# schmatic2.net
KiCad netlist of a schematic drawn in EAGLE
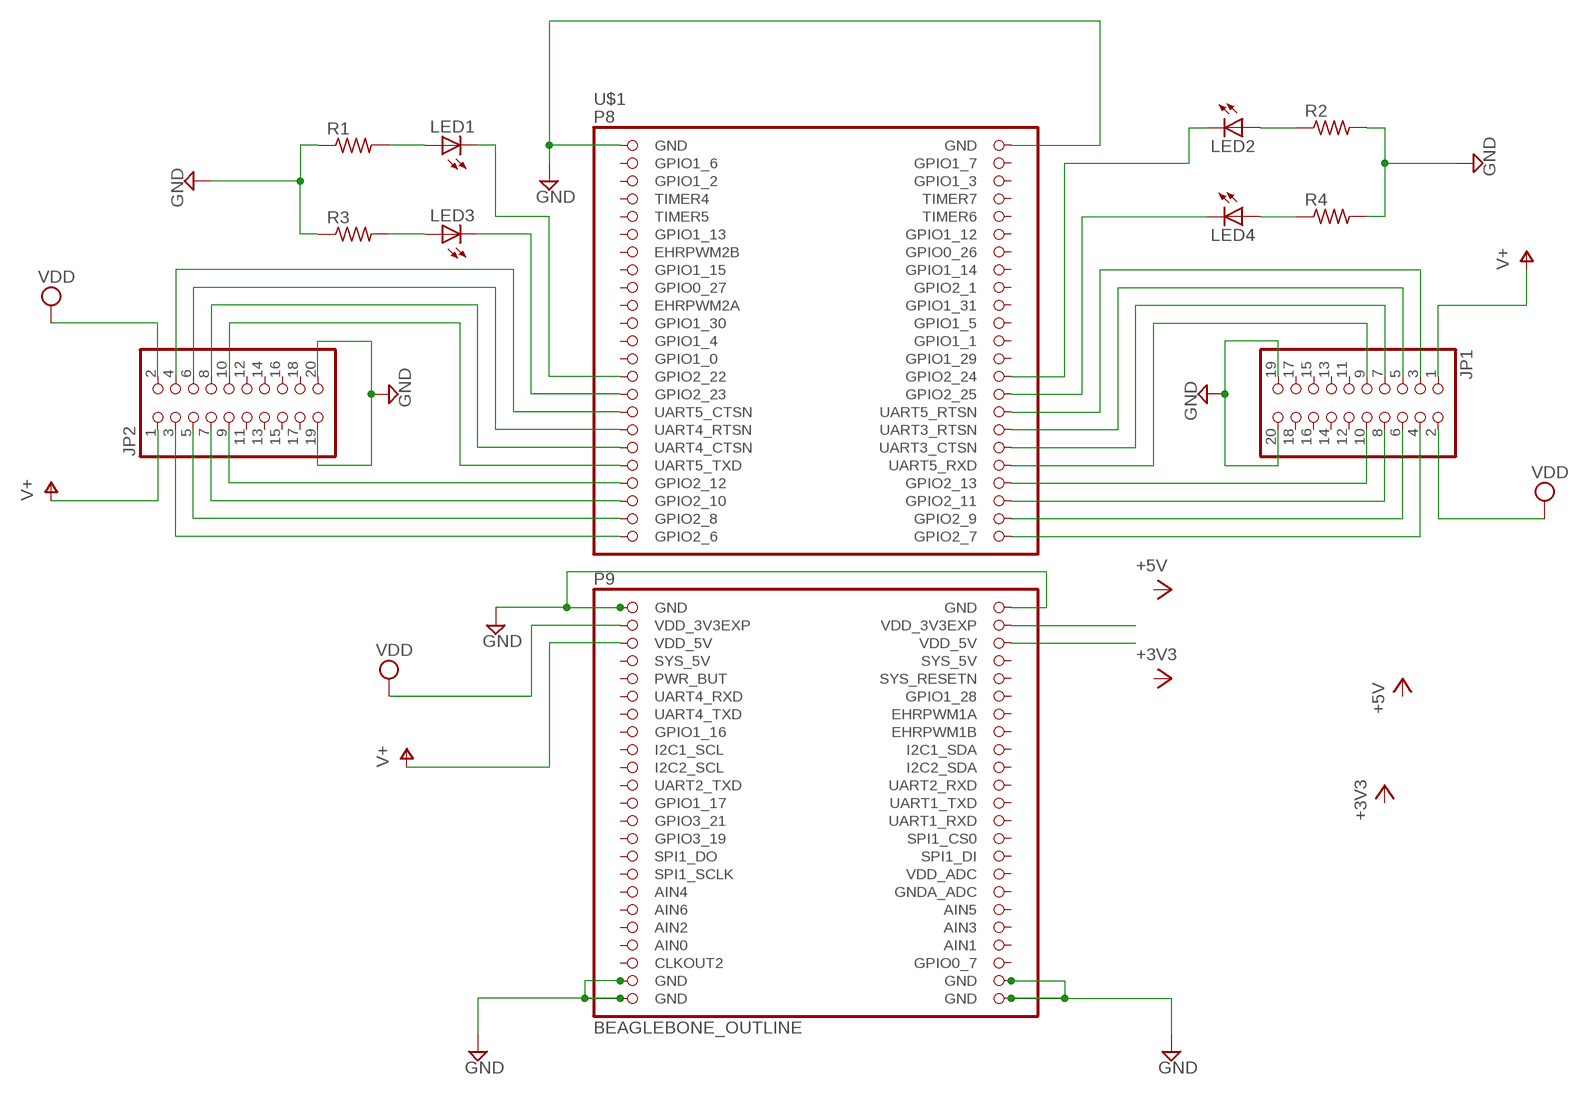
[diagram p0: schematic, sheet 1]

(export (version "E")
  (design (tool "Eeschema 10.0.6"))
  (components
    (comp (ref "JP1")
      (value "PINHD-2X10")
      (footprint "eagle-import:2X10")
      (libsource (lib "eagle-import") (part "PINHD-2X10"))
    )
    (comp (ref "JP2")
      (value "PINHD-2X10")
      (footprint "eagle-import:2X10")
      (libsource (lib "eagle-import") (part "PINHD-2X10"))
    )
    (comp (ref "LED1")
      (value "LED3MM")
      (footprint "eagle-import:LED3MM")
      (libsource (lib "eagle-import") (part "LED3MM"))
    )
    (comp (ref "LED2")
      (value "LED3MM")
      (footprint "eagle-import:LED3MM")
      (libsource (lib "eagle-import") (part "LED3MM"))
    )
    (comp (ref "LED3")
      (value "LED3MM")
      (footprint "eagle-import:LED3MM")
      (libsource (lib "eagle-import") (part "LED3MM"))
    )
    (comp (ref "LED4")
      (value "LED3MM")
      (footprint "eagle-import:LED3MM")
      (libsource (lib "eagle-import") (part "LED3MM"))
    )
    (comp (ref "R1")
      (value "R-US_0309/12")
      (footprint "eagle-import:0309_12")
      (libsource (lib "eagle-import") (part "R-US_0309/12"))
    )
    (comp (ref "R2")
      (value "R-US_0309/12")
      (footprint "eagle-import:0309_12")
      (libsource (lib "eagle-import") (part "R-US_0309/12"))
    )
    (comp (ref "R3")
      (value "R-US_0309/12")
      (footprint "eagle-import:0309_12")
      (libsource (lib "eagle-import") (part "R-US_0309/12"))
    )
    (comp (ref "R4")
      (value "R-US_0309/12")
      (footprint "eagle-import:0309_12")
      (libsource (lib "eagle-import") (part "R-US_0309/12"))
    )
    (comp (ref "U$1")
      (value "BEAGLEBONE_OUTLINE")
      (footprint "eagle-import:BEAGLEBONE_SHIELD")
      (libsource (lib "eagle-import") (part "BEAGLEBONE_OUTLINE"))
    )
  )
  (nets
    (net (code "3") (name "/AIN0") (class "Default")
      (node (ref "U$1") (pin "85") (pinfunction "AIN0_85") (pintype "power_in"))
    )
    (net (code "4") (name "/SYS_5V") (class "Default")
      (node (ref "U$1") (pin "53") (pinfunction "SYS_5V_53") (pintype "power_in"))
    )
    (net (code "5") (name "GND") (class "Default")
      (node (ref "JP1") (pin "19") (pinfunction "19_19") (pintype "passive"))
      (node (ref "JP1") (pin "20") (pinfunction "20_20") (pintype "passive"))
      (node (ref "JP2") (pin "19") (pinfunction "19_19") (pintype "passive"))
      (node (ref "JP2") (pin "20") (pinfunction "20_20") (pintype "passive"))
      (node (ref "R1") (pin "1") (pinfunction "1_1") (pintype "passive"))
      (node (ref "R2") (pin "2") (pinfunction "2_2") (pintype "passive"))
      (node (ref "R3") (pin "1") (pinfunction "1_1") (pintype "passive"))
      (node (ref "R4") (pin "2") (pinfunction "2_2") (pintype "passive"))
      (node (ref "U$1") (pin "1") (pinfunction "GND_1") (pintype "power_in"))
      (node (ref "U$1") (pin "2") (pinfunction "GND_2") (pintype "power_in"))
      (node (ref "U$1") (pin "47") (pinfunction "GND_47") (pintype "power_in"))
      (node (ref "U$1") (pin "48") (pinfunction "GND_48") (pintype "power_in"))
      (node (ref "U$1") (pin "89") (pinfunction "GND_89") (pintype "power_in"))
      (node (ref "U$1") (pin "90") (pinfunction "GND_90") (pintype "power_in"))
      (node (ref "U$1") (pin "91") (pinfunction "GND_91") (pintype "power_in"))
      (node (ref "U$1") (pin "92") (pinfunction "GND_92") (pintype "power_in"))
    )
    (net (code "6") (name "Net-(LED1-C)") (class "Default")
      (node (ref "LED1") (pin "K") (pinfunction "C_K") (pintype "passive"))
      (node (ref "U$1") (pin "27") (pinfunction "GPIO2_22_27") (pintype "passive"))
    )
    (net (code "7") (name "Net-(LED1-PadA)") (class "Default")
      (node (ref "LED1") (pin "A") (pinfunction "A_A") (pintype "passive"))
      (node (ref "R1") (pin "2") (pinfunction "2_2") (pintype "passive"))
    )
    (net (code "8") (name "Net-(LED2-C)") (class "Default")
      (node (ref "LED2") (pin "K") (pinfunction "C_K") (pintype "passive"))
      (node (ref "U$1") (pin "28") (pinfunction "GPIO2_24_28") (pintype "passive"))
    )
    (net (code "9") (name "Net-(LED2-PadA)") (class "Default")
      (node (ref "LED2") (pin "A") (pinfunction "A_A") (pintype "passive"))
      (node (ref "R2") (pin "1") (pinfunction "1_1") (pintype "passive"))
    )
    (net (code "10") (name "Net-(LED3-C)") (class "Default")
      (node (ref "LED3") (pin "K") (pinfunction "C_K") (pintype "passive"))
      (node (ref "U$1") (pin "29") (pinfunction "GPIO2_23_29") (pintype "passive"))
    )
    (net (code "11") (name "Net-(LED3-PadA)") (class "Default")
      (node (ref "LED3") (pin "A") (pinfunction "A_A") (pintype "passive"))
      (node (ref "R3") (pin "2") (pinfunction "2_2") (pintype "passive"))
    )
    (net (code "12") (name "Net-(LED4-C)") (class "Default")
      (node (ref "LED4") (pin "K") (pinfunction "C_K") (pintype "passive"))
      (node (ref "U$1") (pin "30") (pinfunction "GPIO2_25_30") (pintype "passive"))
    )
    (net (code "13") (name "Net-(LED4-PadA)") (class "Default")
      (node (ref "LED4") (pin "A") (pinfunction "A_A") (pintype "passive"))
      (node (ref "R4") (pin "1") (pinfunction "1_1") (pintype "passive"))
    )
    (net (code "14") (name "Net-(U$1-GPIO2_6)") (class "Default")
      (node (ref "JP2") (pin "3") (pinfunction "3_3") (pintype "passive"))
      (node (ref "U$1") (pin "45") (pinfunction "GPIO2_6_45") (pintype "passive"))
    )
    (net (code "15") (name "Net-(U$1-GPIO2_7)") (class "Default")
      (node (ref "JP1") (pin "4") (pinfunction "4_4") (pintype "passive"))
      (node (ref "U$1") (pin "46") (pinfunction "GPIO2_7_46") (pintype "passive"))
    )
    (net (code "16") (name "Net-(U$1-GPIO2_8)") (class "Default")
      (node (ref "JP2") (pin "5") (pinfunction "5_5") (pintype "passive"))
      (node (ref "U$1") (pin "43") (pinfunction "GPIO2_8_43") (pintype "passive"))
    )
    (net (code "17") (name "Net-(U$1-GPIO2_9)") (class "Default")
      (node (ref "JP1") (pin "6") (pinfunction "6_6") (pintype "passive"))
      (node (ref "U$1") (pin "44") (pinfunction "GPIO2_9_44") (pintype "passive"))
    )
    (net (code "18") (name "Net-(U$1-GPIO2_10)") (class "Default")
      (node (ref "JP2") (pin "7") (pinfunction "7_7") (pintype "passive"))
      (node (ref "U$1") (pin "41") (pinfunction "GPIO2_10_41") (pintype "passive"))
    )
    (net (code "19") (name "Net-(U$1-GPIO2_11)") (class "Default")
      (node (ref "JP1") (pin "8") (pinfunction "8_8") (pintype "passive"))
      (node (ref "U$1") (pin "42") (pinfunction "GPIO2_11_42") (pintype "passive"))
    )
    (net (code "20") (name "Net-(U$1-GPIO2_12)") (class "Default")
      (node (ref "JP2") (pin "9") (pinfunction "9_9") (pintype "passive"))
      (node (ref "U$1") (pin "39") (pinfunction "GPIO2_12_39") (pintype "passive"))
    )
    (net (code "21") (name "Net-(U$1-GPIO2_13)") (class "Default")
      (node (ref "JP1") (pin "10") (pinfunction "10_10") (pintype "passive"))
      (node (ref "U$1") (pin "40") (pinfunction "GPIO2_13_40") (pintype "passive"))
    )
    (net (code "22") (name "Net-(U$1-UART3_CTSN)") (class "Default")
      (node (ref "JP1") (pin "7") (pinfunction "7_7") (pintype "passive"))
      (node (ref "U$1") (pin "36") (pinfunction "UART3_CTSN_36") (pintype "passive"))
    )
    (net (code "23") (name "Net-(U$1-UART3_RTSN)") (class "Default")
      (node (ref "JP1") (pin "5") (pinfunction "5_5") (pintype "passive"))
      (node (ref "U$1") (pin "34") (pinfunction "UART3_RTSN_34") (pintype "passive"))
    )
    (net (code "24") (name "Net-(U$1-UART4_CTSN)") (class "Default")
      (node (ref "JP2") (pin "8") (pinfunction "8_8") (pintype "passive"))
      (node (ref "U$1") (pin "35") (pinfunction "UART4_CTSN_35") (pintype "passive"))
    )
    (net (code "25") (name "Net-(U$1-UART4_RTSN)") (class "Default")
      (node (ref "JP2") (pin "6") (pinfunction "6_6") (pintype "passive"))
      (node (ref "U$1") (pin "33") (pinfunction "UART4_RTSN_33") (pintype "passive"))
    )
    (net (code "26") (name "Net-(U$1-UART5_CTSN)") (class "Default")
      (node (ref "JP2") (pin "4") (pinfunction "4_4") (pintype "passive"))
      (node (ref "U$1") (pin "31") (pinfunction "UART5_CTSN_31") (pintype "passive"))
    )
    (net (code "27") (name "Net-(U$1-UART5_RTSN)") (class "Default")
      (node (ref "JP1") (pin "3") (pinfunction "3_3") (pintype "passive"))
      (node (ref "U$1") (pin "32") (pinfunction "UART5_RTSN_32") (pintype "passive"))
    )
    (net (code "28") (name "Net-(U$1-UART5_RXD)") (class "Default")
      (node (ref "JP1") (pin "9") (pinfunction "9_9") (pintype "passive"))
      (node (ref "U$1") (pin "38") (pinfunction "UART5_RXD_38") (pintype "passive"))
    )
    (net (code "29") (name "Net-(U$1-UART5_TXD)") (class "Default")
      (node (ref "JP2") (pin "10") (pinfunction "10_10") (pintype "passive"))
      (node (ref "U$1") (pin "37") (pinfunction "UART5_TXD_37") (pintype "passive"))
    )
    (net (code "30") (name "V+") (class "Default")
      (node (ref "JP1") (pin "1") (pinfunction "1_1") (pintype "passive"))
      (node (ref "JP2") (pin "1") (pinfunction "1_1") (pintype "passive"))
      (node (ref "U$1") (pin "51") (pinfunction "VDD_5V_51") (pintype "power_in"))
    )
    (net (code "31") (name "VDD") (class "Default")
      (node (ref "JP1") (pin "2") (pinfunction "2_2") (pintype "passive"))
      (node (ref "JP2") (pin "2") (pinfunction "2_2") (pintype "passive"))
      (node (ref "U$1") (pin "49") (pinfunction "VDD_3V3EXP_49") (pintype "power_in"))
    )
    (net (code "32") (name "unconnected-(JP1-Pad11)") (class "Default")
      (node (ref "JP1") (pin "11") (pinfunction "11_11") (pintype "passive"))
    )
    (net (code "33") (name "unconnected-(JP1-Pad12)") (class "Default")
      (node (ref "JP1") (pin "12") (pinfunction "12_12") (pintype "passive"))
    )
    (net (code "34") (name "unconnected-(JP1-Pad13)") (class "Default")
      (node (ref "JP1") (pin "13") (pinfunction "13_13") (pintype "passive"))
    )
    (net (code "35") (name "unconnected-(JP1-Pad14)") (class "Default")
      (node (ref "JP1") (pin "14") (pinfunction "14_14") (pintype "passive"))
    )
    (net (code "36") (name "unconnected-(JP1-Pad15)") (class "Default")
      (node (ref "JP1") (pin "15") (pinfunction "15_15") (pintype "passive"))
    )
    (net (code "37") (name "unconnected-(JP1-Pad16)") (class "Default")
      (node (ref "JP1") (pin "16") (pinfunction "16_16") (pintype "passive"))
    )
    (net (code "38") (name "unconnected-(JP1-Pad17)") (class "Default")
      (node (ref "JP1") (pin "17") (pinfunction "17_17") (pintype "passive"))
    )
    (net (code "39") (name "unconnected-(JP1-Pad18)") (class "Default")
      (node (ref "JP1") (pin "18") (pinfunction "18_18") (pintype "passive"))
    )
    (net (code "40") (name "unconnected-(JP2-Pad11)") (class "Default")
      (node (ref "JP2") (pin "11") (pinfunction "11_11") (pintype "passive"))
    )
    (net (code "41") (name "unconnected-(JP2-Pad12)") (class "Default")
      (node (ref "JP2") (pin "12") (pinfunction "12_12") (pintype "passive"))
    )
    (net (code "42") (name "unconnected-(JP2-Pad13)") (class "Default")
      (node (ref "JP2") (pin "13") (pinfunction "13_13") (pintype "passive"))
    )
    (net (code "43") (name "unconnected-(JP2-Pad14)") (class "Default")
      (node (ref "JP2") (pin "14") (pinfunction "14_14") (pintype "passive"))
    )
    (net (code "44") (name "unconnected-(JP2-Pad15)") (class "Default")
      (node (ref "JP2") (pin "15") (pinfunction "15_15") (pintype "passive"))
    )
    (net (code "45") (name "unconnected-(JP2-Pad16)") (class "Default")
      (node (ref "JP2") (pin "16") (pinfunction "16_16") (pintype "passive"))
    )
    (net (code "46") (name "unconnected-(JP2-Pad17)") (class "Default")
      (node (ref "JP2") (pin "17") (pinfunction "17_17") (pintype "passive"))
    )
    (net (code "47") (name "unconnected-(JP2-Pad18)") (class "Default")
      (node (ref "JP2") (pin "18") (pinfunction "18_18") (pintype "passive"))
    )
    (net (code "48") (name "unconnected-(U$1-AIN1-Pad86)") (class "Default")
      (node (ref "U$1") (pin "86") (pinfunction "AIN1_86") (pintype "passive"))
    )
    (net (code "49") (name "unconnected-(U$1-AIN2-Pad83)") (class "Default")
      (node (ref "U$1") (pin "83") (pinfunction "AIN2_83") (pintype "passive"))
    )
    (net (code "50") (name "unconnected-(U$1-AIN3-Pad84)") (class "Default")
      (node (ref "U$1") (pin "84") (pinfunction "AIN3_84") (pintype "passive"))
    )
    (net (code "51") (name "unconnected-(U$1-AIN4-Pad79)") (class "Default")
      (node (ref "U$1") (pin "79") (pinfunction "AIN4_79") (pintype "passive"))
    )
    (net (code "52") (name "unconnected-(U$1-AIN5-Pad82)") (class "Default")
      (node (ref "U$1") (pin "82") (pinfunction "AIN5_82") (pintype "passive"))
    )
    (net (code "53") (name "unconnected-(U$1-AIN6-Pad81)") (class "Default")
      (node (ref "U$1") (pin "81") (pinfunction "AIN6_81") (pintype "passive"))
    )
    (net (code "54") (name "unconnected-(U$1-CLKOUT2-Pad87)") (class "Default")
      (node (ref "U$1") (pin "87") (pinfunction "CLKOUT2_87") (pintype "input"))
    )
    (net (code "55") (name "unconnected-(U$1-EHRPWM1A-Pad60)") (class "Default")
      (node (ref "U$1") (pin "60") (pinfunction "EHRPWM1A_60") (pintype "passive"))
    )
    (net (code "56") (name "unconnected-(U$1-EHRPWM1B-Pad62)") (class "Default")
      (node (ref "U$1") (pin "62") (pinfunction "EHRPWM1B_62") (pintype "passive"))
    )
    (net (code "57") (name "unconnected-(U$1-EHRPWM2A-Pad19)") (class "Default")
      (node (ref "U$1") (pin "19") (pinfunction "EHRPWM2A_19") (pintype "passive"))
    )
    (net (code "58") (name "unconnected-(U$1-EHRPWM2B-Pad13)") (class "Default")
      (node (ref "U$1") (pin "13") (pinfunction "EHRPWM2B_13") (pintype "passive"))
    )
    (net (code "59") (name "unconnected-(U$1-GNDA_ADC-Pad80)") (class "Default")
      (node (ref "U$1") (pin "80") (pinfunction "GNDA_ADC_80") (pintype "passive"))
    )
    (net (code "60") (name "unconnected-(U$1-GPIO0_7-Pad88)") (class "Default")
      (node (ref "U$1") (pin "88") (pinfunction "GPIO0_7_88") (pintype "passive"))
    )
    (net (code "61") (name "unconnected-(U$1-GPIO0_26-Pad14)") (class "Default")
      (node (ref "U$1") (pin "14") (pinfunction "GPIO0_26_14") (pintype "passive"))
    )
    (net (code "62") (name "unconnected-(U$1-GPIO0_27-Pad17)") (class "Default")
      (node (ref "U$1") (pin "17") (pinfunction "GPIO0_27_17") (pintype "passive"))
    )
    (net (code "63") (name "unconnected-(U$1-GPIO1_0-Pad25)") (class "Default")
      (node (ref "U$1") (pin "25") (pinfunction "GPIO1_0_25") (pintype "passive"))
    )
    (net (code "64") (name "unconnected-(U$1-GPIO1_1-Pad24)") (class "Default")
      (node (ref "U$1") (pin "24") (pinfunction "GPIO1_1_24") (pintype "passive"))
    )
    (net (code "65") (name "unconnected-(U$1-GPIO1_2-Pad5)") (class "Default")
      (node (ref "U$1") (pin "5") (pinfunction "GPIO1_2_5") (pintype "passive"))
    )
    (net (code "66") (name "unconnected-(U$1-GPIO1_3-Pad6)") (class "Default")
      (node (ref "U$1") (pin "6") (pinfunction "GPIO1_3_6") (pintype "passive"))
    )
    (net (code "67") (name "unconnected-(U$1-GPIO1_4-Pad23)") (class "Default")
      (node (ref "U$1") (pin "23") (pinfunction "GPIO1_4_23") (pintype "passive"))
    )
    (net (code "68") (name "unconnected-(U$1-GPIO1_5-Pad22)") (class "Default")
      (node (ref "U$1") (pin "22") (pinfunction "GPIO1_5_22") (pintype "passive"))
    )
    (net (code "69") (name "unconnected-(U$1-GPIO1_6-Pad3)") (class "Default")
      (node (ref "U$1") (pin "3") (pinfunction "GPIO1_6_3") (pintype "passive"))
    )
    (net (code "70") (name "unconnected-(U$1-GPIO1_7-Pad4)") (class "Default")
      (node (ref "U$1") (pin "4") (pinfunction "GPIO1_7_4") (pintype "passive"))
    )
    (net (code "71") (name "unconnected-(U$1-GPIO1_12-Pad12)") (class "Default")
      (node (ref "U$1") (pin "12") (pinfunction "GPIO1_12_12") (pintype "passive"))
    )
    (net (code "72") (name "unconnected-(U$1-GPIO1_13-Pad11)") (class "Default")
      (node (ref "U$1") (pin "11") (pinfunction "GPIO1_13_11") (pintype "passive"))
    )
    (net (code "73") (name "unconnected-(U$1-GPIO1_14-Pad16)") (class "Default")
      (node (ref "U$1") (pin "16") (pinfunction "GPIO1_14_16") (pintype "passive"))
    )
    (net (code "74") (name "unconnected-(U$1-GPIO1_15-Pad15)") (class "Default")
      (node (ref "U$1") (pin "15") (pinfunction "GPIO1_15_15") (pintype "passive"))
    )
    (net (code "75") (name "unconnected-(U$1-GPIO1_16-Pad61)") (class "Default")
      (node (ref "U$1") (pin "61") (pinfunction "GPIO1_16_61") (pintype "passive"))
    )
    (net (code "76") (name "unconnected-(U$1-GPIO1_17-Pad69)") (class "Default")
      (node (ref "U$1") (pin "69") (pinfunction "GPIO1_17_69") (pintype "passive"))
    )
    (net (code "77") (name "unconnected-(U$1-GPIO1_28-Pad58)") (class "Default")
      (node (ref "U$1") (pin "58") (pinfunction "GPIO1_28_58") (pintype "passive"))
    )
    (net (code "78") (name "unconnected-(U$1-GPIO1_29-Pad26)") (class "Default")
      (node (ref "U$1") (pin "26") (pinfunction "GPIO1_29_26") (pintype "passive"))
    )
    (net (code "79") (name "unconnected-(U$1-GPIO1_30-Pad21)") (class "Default")
      (node (ref "U$1") (pin "21") (pinfunction "GPIO1_30_21") (pintype "passive"))
    )
    (net (code "80") (name "unconnected-(U$1-GPIO1_31-Pad20)") (class "Default")
      (node (ref "U$1") (pin "20") (pinfunction "GPIO1_31_20") (pintype "passive"))
    )
    (net (code "81") (name "unconnected-(U$1-GPIO2_1-Pad18)") (class "Default")
      (node (ref "U$1") (pin "18") (pinfunction "GPIO2_1_18") (pintype "passive"))
    )
    (net (code "82") (name "unconnected-(U$1-GPIO3_19-Pad73)") (class "Default")
      (node (ref "U$1") (pin "73") (pinfunction "GPIO3_19_73") (pintype "passive"))
    )
    (net (code "83") (name "unconnected-(U$1-GPIO3_21-Pad71)") (class "Default")
      (node (ref "U$1") (pin "71") (pinfunction "GPIO3_21_71") (pintype "passive"))
    )
    (net (code "84") (name "unconnected-(U$1-I2C1_SCL-Pad63)") (class "Default")
      (node (ref "U$1") (pin "63") (pinfunction "I2C1_SCL_63") (pintype "passive"))
    )
    (net (code "85") (name "unconnected-(U$1-I2C1_SDA-Pad64)") (class "Default")
      (node (ref "U$1") (pin "64") (pinfunction "I2C1_SDA_64") (pintype "passive"))
    )
    (net (code "86") (name "unconnected-(U$1-I2C2_SCL-Pad65)") (class "Default")
      (node (ref "U$1") (pin "65") (pinfunction "I2C2_SCL_65") (pintype "passive"))
    )
    (net (code "87") (name "unconnected-(U$1-I2C2_SDA-Pad66)") (class "Default")
      (node (ref "U$1") (pin "66") (pinfunction "I2C2_SDA_66") (pintype "passive"))
    )
    (net (code "88") (name "unconnected-(U$1-PWR_BUT-Pad55)") (class "Default")
      (node (ref "U$1") (pin "55") (pinfunction "PWR_BUT_55") (pintype "passive"))
    )
    (net (code "89") (name "unconnected-(U$1-SPI1_CS0-Pad74)") (class "Default")
      (node (ref "U$1") (pin "74") (pinfunction "SPI1_CS0_74") (pintype "passive"))
    )
    (net (code "90") (name "unconnected-(U$1-SPI1_DI-Pad76)") (class "Default")
      (node (ref "U$1") (pin "76") (pinfunction "SPI1_DI_76") (pintype "passive"))
    )
    (net (code "91") (name "unconnected-(U$1-SPI1_DO-Pad75)") (class "Default")
      (node (ref "U$1") (pin "75") (pinfunction "SPI1_DO_75") (pintype "passive"))
    )
    (net (code "92") (name "unconnected-(U$1-SPI1_SCLK-Pad77)") (class "Default")
      (node (ref "U$1") (pin "77") (pinfunction "SPI1_SCLK_77") (pintype "passive"))
    )
    (net (code "93") (name "unconnected-(U$1-SYS_5V-Pad54)") (class "Default")
      (node (ref "U$1") (pin "54") (pinfunction "SYS_5V_54") (pintype "passive"))
    )
    (net (code "94") (name "unconnected-(U$1-SYS_RESETN-Pad56)") (class "Default")
      (node (ref "U$1") (pin "56") (pinfunction "SYS_RESETN_56") (pintype "passive"))
    )
    (net (code "95") (name "unconnected-(U$1-TIMER4-Pad7)") (class "Default")
      (node (ref "U$1") (pin "7") (pinfunction "TIMER4_7") (pintype "passive"))
    )
    (net (code "96") (name "unconnected-(U$1-TIMER5-Pad9)") (class "Default")
      (node (ref "U$1") (pin "9") (pinfunction "TIMER5_9") (pintype "passive"))
    )
    (net (code "97") (name "unconnected-(U$1-TIMER6-Pad10)") (class "Default")
      (node (ref "U$1") (pin "10") (pinfunction "TIMER6_10") (pintype "passive"))
    )
    (net (code "98") (name "unconnected-(U$1-TIMER7-Pad8)") (class "Default")
      (node (ref "U$1") (pin "8") (pinfunction "TIMER7_8") (pintype "passive"))
    )
    (net (code "99") (name "unconnected-(U$1-UART1_RXD-Pad72)") (class "Default")
      (node (ref "U$1") (pin "72") (pinfunction "UART1_RXD_72") (pintype "passive"))
    )
    (net (code "100") (name "unconnected-(U$1-UART1_TXD-Pad70)") (class "Default")
      (node (ref "U$1") (pin "70") (pinfunction "UART1_TXD_70") (pintype "passive"))
    )
    (net (code "101") (name "unconnected-(U$1-UART2_RXD-Pad68)") (class "Default")
      (node (ref "U$1") (pin "68") (pinfunction "UART2_RXD_68") (pintype "passive"))
    )
    (net (code "102") (name "unconnected-(U$1-UART2_TXD-Pad67)") (class "Default")
      (node (ref "U$1") (pin "67") (pinfunction "UART2_TXD_67") (pintype "passive"))
    )
    (net (code "103") (name "unconnected-(U$1-UART4_RXD-Pad57)") (class "Default")
      (node (ref "U$1") (pin "57") (pinfunction "UART4_RXD_57") (pintype "passive"))
    )
    (net (code "104") (name "unconnected-(U$1-UART4_TXD-Pad59)") (class "Default")
      (node (ref "U$1") (pin "59") (pinfunction "UART4_TXD_59") (pintype "passive"))
    )
    (net (code "105") (name "unconnected-(U$1-VDD_3V3EXP-Pad50)") (class "Default")
      (node (ref "U$1") (pin "50") (pinfunction "VDD_3V3EXP_50") (pintype "power_in"))
    )
    (net (code "106") (name "unconnected-(U$1-VDD_5V-Pad52)") (class "Default")
      (node (ref "U$1") (pin "52") (pinfunction "VDD_5V_52") (pintype "power_in"))
    )
    (net (code "107") (name "unconnected-(U$1-VDD_ADC-Pad78)") (class "Default")
      (node (ref "U$1") (pin "78") (pinfunction "VDD_ADC_78") (pintype "passive"))
    )
  )
)
